# FMC_SDR_top.net
KiCad netlist of a schematic drawn in Altium Designer
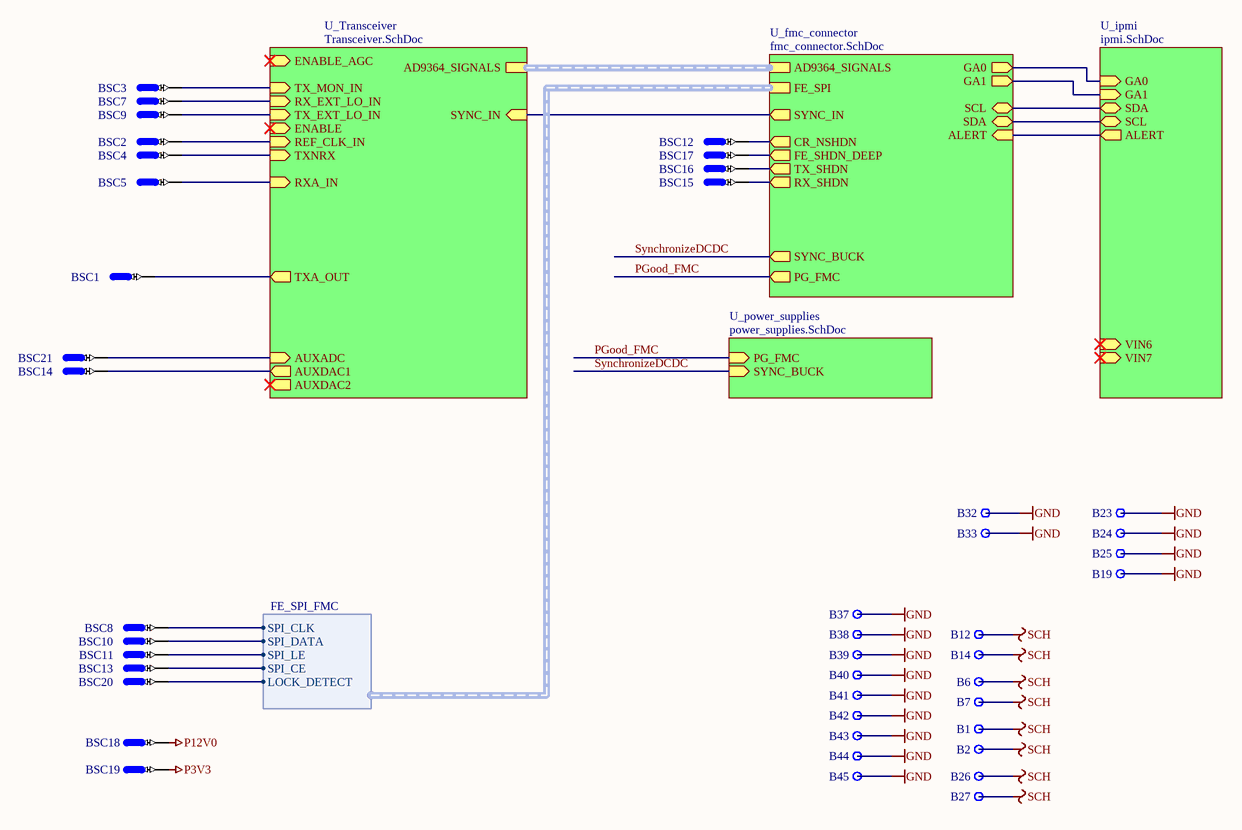
[diagram p0: FMC_SDR_top.SchDoc]

(export (version "E")
  (design (tool "Eeschema 10.0.6"))
  (components
    (comp (ref "B1")
      (value "Plated Hole")
      (footprint "MTG240_400")
      (description "Single Terminal Socket")
      (fields (field (name "PART NUMBER") "PLATED_HOLE2.4_PAD4.0") (field (name "AUTHOR") "CERN DEM JMW"))
      (libsource (lib "Eletro-mechanical") (part "Single Terminal Socket"))
    )
    (comp (ref "B2")
      (value "Plated Hole")
      (footprint "MTG240_400")
      (description "Single Terminal Socket")
      (fields (field (name "PART NUMBER") "PLATED_HOLE2.4_PAD4.0") (field (name "AUTHOR") "CERN DEM JMW"))
      (libsource (lib "Eletro-mechanical") (part "Single Terminal Socket"))
    )
    (comp (ref "B6")
      (value "Plated Hole")
      (footprint "MTG240_400")
      (description "Single Terminal Socket")
      (fields (field (name "PART NUMBER") "PLATED_HOLE2.4_PAD4.0") (field (name "AUTHOR") "CERN DEM JMW"))
      (libsource (lib "Eletro-mechanical") (part "Single Terminal Socket"))
    )
    (comp (ref "B7")
      (value "Plated Hole")
      (footprint "MTG240_400")
      (description "Single Terminal Socket")
      (fields (field (name "PART NUMBER") "PLATED_HOLE2.4_PAD4.0") (field (name "AUTHOR") "CERN DEM JMW"))
      (libsource (lib "Eletro-mechanical") (part "Single Terminal Socket"))
    )
    (comp (ref "B12")
      (value "Plated Hole")
      (footprint "MTG240_400")
      (description "Single Terminal Socket")
      (fields (field (name "PART NUMBER") "PLATED_HOLE2.4_PAD4.0") (field (name "AUTHOR") "CERN DEM JMW"))
      (libsource (lib "Eletro-mechanical") (part "Single Terminal Socket"))
    )
    (comp (ref "B14")
      (value "Plated Hole")
      (footprint "MTG240_400")
      (description "Single Terminal Socket")
      (fields (field (name "PART NUMBER") "PLATED_HOLE2.4_PAD4.0") (field (name "AUTHOR") "CERN DEM JMW"))
      (libsource (lib "Eletro-mechanical") (part "Single Terminal Socket"))
    )
    (comp (ref "B19")
      (value "Plated Hole")
      (footprint "MTG270_500")
      (description "Single Terminal Socket")
      (fields (field (name "PART NUMBER") "PLATED_HOLE2.7_PAD5.0") (field (name "AUTHOR") "CERN DEM JMW"))
      (libsource (lib "") (part "Single Terminal Socket_1"))
    )
    (comp (ref "B23")
      (value "Plated Hole")
      (footprint "MTG270_500")
      (description "Single Terminal Socket")
      (fields (field (name "PART NUMBER") "PLATED_HOLE2.7_PAD5.0") (field (name "AUTHOR") "CERN DEM JMW"))
      (libsource (lib "") (part "Single Terminal Socket_1"))
    )
    (comp (ref "B24")
      (value "Plated Hole")
      (footprint "MTG270_500")
      (description "Single Terminal Socket")
      (fields (field (name "PART NUMBER") "PLATED_HOLE2.7_PAD5.0") (field (name "AUTHOR") "CERN DEM JMW"))
      (libsource (lib "") (part "Single Terminal Socket_1"))
    )
    (comp (ref "B25")
      (value "Plated Hole")
      (footprint "MTG270_500")
      (description "Single Terminal Socket")
      (fields (field (name "PART NUMBER") "PLATED_HOLE2.7_PAD5.0") (field (name "AUTHOR") "CERN DEM JMW"))
      (libsource (lib "") (part "Single Terminal Socket_1"))
    )
    (comp (ref "B26")
      (value "Plated Hole")
      (footprint "MTG240_400")
      (description "Single Terminal Socket")
      (fields (field (name "PART NUMBER") "PLATED_HOLE2.4_PAD4.0") (field (name "AUTHOR") "CERN DEM JMW"))
      (libsource (lib "Eletro-mechanical") (part "Single Terminal Socket"))
    )
    (comp (ref "B27")
      (value "Plated Hole")
      (footprint "MTG240_400")
      (description "Single Terminal Socket")
      (fields (field (name "PART NUMBER") "PLATED_HOLE2.4_PAD4.0") (field (name "AUTHOR") "CERN DEM JMW"))
      (libsource (lib "Eletro-mechanical") (part "Single Terminal Socket"))
    )
    (comp (ref "B32")
      (value "Plated Hole")
      (footprint "MTG240_400")
      (description "Single Terminal Socket")
      (fields (field (name "PART NUMBER") "PLATED_HOLE2.4_PAD4.0") (field (name "AUTHOR") "CERN DEM JMW"))
      (libsource (lib "Eletro-mechanical") (part "Single Terminal Socket"))
    )
    (comp (ref "B33")
      (value "Plated Hole")
      (footprint "MTG240_400")
      (description "Single Terminal Socket")
      (fields (field (name "PART NUMBER") "PLATED_HOLE2.4_PAD4.0") (field (name "AUTHOR") "CERN DEM JMW"))
      (libsource (lib "Eletro-mechanical") (part "Single Terminal Socket"))
    )
    (comp (ref "B37")
      (value "Plated Hole")
      (footprint "MTG240_400")
      (description "Single Terminal Socket")
      (fields (field (name "PART NUMBER") "PLATED_HOLE2.4_PAD4.0") (field (name "AUTHOR") "CERN DEM JMW"))
      (libsource (lib "Eletro-mechanical") (part "Single Terminal Socket"))
    )
    (comp (ref "B38")
      (value "Plated Hole")
      (footprint "MTG240_400")
      (description "Single Terminal Socket")
      (fields (field (name "PART NUMBER") "PLATED_HOLE2.4_PAD4.0") (field (name "AUTHOR") "CERN DEM JMW"))
      (libsource (lib "Eletro-mechanical") (part "Single Terminal Socket"))
    )
    (comp (ref "B39")
      (value "Plated Hole")
      (footprint "MTG240_400")
      (description "Single Terminal Socket")
      (fields (field (name "PART NUMBER") "PLATED_HOLE2.4_PAD4.0") (field (name "AUTHOR") "CERN DEM JMW"))
      (libsource (lib "Eletro-mechanical") (part "Single Terminal Socket"))
    )
    (comp (ref "B40")
      (value "Plated Hole")
      (footprint "MTG240_400")
      (description "Single Terminal Socket")
      (fields (field (name "PART NUMBER") "PLATED_HOLE2.4_PAD4.0") (field (name "AUTHOR") "CERN DEM JMW"))
      (libsource (lib "Eletro-mechanical") (part "Single Terminal Socket"))
    )
    (comp (ref "B41")
      (value "Plated Hole")
      (footprint "MTG240_400")
      (description "Single Terminal Socket")
      (fields (field (name "PART NUMBER") "PLATED_HOLE2.4_PAD4.0") (field (name "AUTHOR") "CERN DEM JMW"))
      (libsource (lib "Eletro-mechanical") (part "Single Terminal Socket"))
    )
    (comp (ref "B42")
      (value "Plated Hole")
      (footprint "MTG240_400")
      (description "Single Terminal Socket")
      (fields (field (name "PART NUMBER") "PLATED_HOLE2.4_PAD4.0") (field (name "AUTHOR") "CERN DEM JMW"))
      (libsource (lib "Eletro-mechanical") (part "Single Terminal Socket"))
    )
    (comp (ref "B43")
      (value "Plated Hole")
      (footprint "MTG240_400")
      (description "Single Terminal Socket")
      (fields (field (name "PART NUMBER") "PLATED_HOLE2.4_PAD4.0") (field (name "AUTHOR") "CERN DEM JMW"))
      (libsource (lib "Eletro-mechanical") (part "Single Terminal Socket"))
    )
    (comp (ref "B44")
      (value "Plated Hole")
      (footprint "MTG240_400")
      (description "Single Terminal Socket")
      (fields (field (name "PART NUMBER") "PLATED_HOLE2.4_PAD4.0") (field (name "AUTHOR") "CERN DEM JMW"))
      (libsource (lib "Eletro-mechanical") (part "Single Terminal Socket"))
    )
    (comp (ref "B45")
      (value "Plated Hole")
      (footprint "MTG240_400")
      (description "Single Terminal Socket")
      (fields (field (name "PART NUMBER") "PLATED_HOLE2.4_PAD4.0") (field (name "AUTHOR") "CERN DEM JMW"))
      (libsource (lib "Eletro-mechanical") (part "Single Terminal Socket"))
    )
    (comp (ref "BSC1")
      (value "0603 Female")
      (footprint "PCB_CONN_0603F")
      (libsource (lib "FMC_SDR") (part "0603_female_BoardSolderConnector"))
    )
    (comp (ref "BSC2")
      (value "0603 Female")
      (footprint "PCB_CONN_0603F")
      (libsource (lib "FMC_SDR") (part "0603_female_BoardSolderConnector"))
    )
    (comp (ref "BSC3")
      (value "0603 Female")
      (footprint "PCB_CONN_0603F")
      (libsource (lib "FMC_SDR") (part "0603_female_BoardSolderConnector"))
    )
    (comp (ref "BSC4")
      (value "0603 Female")
      (footprint "PCB_CONN_0603F")
      (libsource (lib "FMC_SDR") (part "0603_female_BoardSolderConnector"))
    )
    (comp (ref "BSC5")
      (value "0603 Female")
      (footprint "PCB_CONN_0603F")
      (libsource (lib "FMC_SDR") (part "0603_female_BoardSolderConnector"))
    )
    (comp (ref "BSC7")
      (value "0603 Female")
      (footprint "PCB_CONN_0603F")
      (libsource (lib "FMC_SDR") (part "0603_female_BoardSolderConnector"))
    )
    (comp (ref "BSC8")
      (value "0603 Female")
      (footprint "PCB_CONN_0603F")
      (libsource (lib "FMC_SDR") (part "0603_female_BoardSolderConnector"))
    )
    (comp (ref "BSC9")
      (value "0603 Female")
      (footprint "PCB_CONN_0603F")
      (libsource (lib "FMC_SDR") (part "0603_female_BoardSolderConnector"))
    )
    (comp (ref "BSC10")
      (value "0603 Female")
      (footprint "PCB_CONN_0603F")
      (libsource (lib "FMC_SDR") (part "0603_female_BoardSolderConnector"))
    )
    (comp (ref "BSC11")
      (value "0603 Female")
      (footprint "PCB_CONN_0603F")
      (libsource (lib "FMC_SDR") (part "0603_female_BoardSolderConnector"))
    )
    (comp (ref "BSC12")
      (value "0603 Female")
      (footprint "PCB_CONN_0603F")
      (libsource (lib "FMC_SDR") (part "0603_female_BoardSolderConnector"))
    )
    (comp (ref "BSC13")
      (value "0603 Female")
      (footprint "PCB_CONN_0603F")
      (libsource (lib "FMC_SDR") (part "0603_female_BoardSolderConnector"))
    )
    (comp (ref "BSC14")
      (value "0603 Female")
      (footprint "PCB_CONN_0603F")
      (libsource (lib "FMC_SDR") (part "0603_female_BoardSolderConnector"))
    )
    (comp (ref "BSC15")
      (value "0603 Female")
      (footprint "PCB_CONN_0603F")
      (libsource (lib "FMC_SDR") (part "0603_female_BoardSolderConnector"))
    )
    (comp (ref "BSC16")
      (value "0603 Female")
      (footprint "PCB_CONN_0603F")
      (libsource (lib "FMC_SDR") (part "0603_female_BoardSolderConnector"))
    )
    (comp (ref "BSC17")
      (value "0603 Female")
      (footprint "PCB_CONN_0603F")
      (libsource (lib "FMC_SDR") (part "0603_female_BoardSolderConnector"))
    )
    (comp (ref "BSC18")
      (value "1206 Female")
      (footprint "PCB_CONN_1206F")
      (libsource (lib "FMC_SDR") (part "1206_female_BoardSolderConnector"))
    )
    (comp (ref "BSC19")
      (value "1206 Female")
      (footprint "PCB_CONN_1206F")
      (libsource (lib "FMC_SDR") (part "1206_female_BoardSolderConnector"))
    )
    (comp (ref "BSC20")
      (value "0603 Female")
      (footprint "PCB_CONN_0603F")
      (libsource (lib "FMC_SDR") (part "0603_female_BoardSolderConnector"))
    )
    (comp (ref "BSC21")
      (value "0603 Female")
      (footprint "PCB_CONN_0603F")
      (libsource (lib "FMC_SDR") (part "0603_female_BoardSolderConnector"))
    )
  )
  (nets
    (net (code "4") (name "/AUXADC") (class "Default")
      (node (ref "BSC21") (pin "1") (pinfunction "1_1") (pintype "bidirectional"))
    )
    (net (code "5") (name "/AUXDAC1") (class "Default")
      (node (ref "BSC14") (pin "1") (pinfunction "1_1") (pintype "bidirectional"))
    )
    (net (code "7") (name "/CR_NSHDN") (class "Default")
      (node (ref "BSC12") (pin "1") (pinfunction "1_1") (pintype "bidirectional"))
    )
    (net (code "10") (name "/FE_SHDN_DEEP") (class "Default")
      (node (ref "BSC17") (pin "1") (pinfunction "1_1") (pintype "bidirectional"))
    )
    (net (code "13") (name "/LOCK_DETECT") (class "Default")
      (node (ref "BSC20") (pin "1") (pinfunction "1_1") (pintype "bidirectional"))
    )
    (net (code "15") (name "/REF_CLK_IN") (class "Default")
      (node (ref "BSC2") (pin "1") (pinfunction "1_1") (pintype "bidirectional"))
    )
    (net (code "16") (name "/RXA_IN") (class "Default")
      (node (ref "BSC5") (pin "1") (pinfunction "1_1") (pintype "bidirectional"))
    )
    (net (code "17") (name "/RX_EXT_LO_IN") (class "Default")
      (node (ref "BSC7") (pin "1") (pinfunction "1_1") (pintype "bidirectional"))
    )
    (net (code "18") (name "/RX_SHDN") (class "Default")
      (node (ref "BSC15") (pin "1") (pinfunction "1_1") (pintype "bidirectional"))
    )
    (net (code "21") (name "/SPI_CE") (class "Default")
      (node (ref "BSC13") (pin "1") (pinfunction "1_1") (pintype "bidirectional"))
    )
    (net (code "22") (name "/SPI_CLK") (class "Default")
      (node (ref "BSC8") (pin "1") (pinfunction "1_1") (pintype "bidirectional"))
    )
    (net (code "23") (name "/SPI_DATA") (class "Default")
      (node (ref "BSC10") (pin "1") (pinfunction "1_1") (pintype "bidirectional"))
    )
    (net (code "24") (name "/SPI_LE") (class "Default")
      (node (ref "BSC11") (pin "1") (pinfunction "1_1") (pintype "bidirectional"))
    )
    (net (code "27") (name "/TXA_OUT") (class "Default")
      (node (ref "BSC1") (pin "1") (pinfunction "1_1") (pintype "bidirectional"))
    )
    (net (code "28") (name "/TXNRX") (class "Default")
      (node (ref "BSC4") (pin "1") (pinfunction "1_1") (pintype "bidirectional"))
    )
    (net (code "29") (name "/TX_EXT_LO_IN") (class "Default")
      (node (ref "BSC9") (pin "1") (pinfunction "1_1") (pintype "bidirectional"))
    )
    (net (code "30") (name "/TX_MON_IN") (class "Default")
      (node (ref "BSC3") (pin "1") (pinfunction "1_1") (pintype "bidirectional"))
    )
    (net (code "31") (name "/TX_SHDN") (class "Default")
      (node (ref "BSC16") (pin "1") (pinfunction "1_1") (pintype "bidirectional"))
    )
    (net (code "35") (name "GND") (class "Default")
      (node (ref "B19") (pin "1") (pinfunction "1_1") (pintype "bidirectional"))
      (node (ref "B23") (pin "1") (pinfunction "1_1") (pintype "bidirectional"))
      (node (ref "B24") (pin "1") (pinfunction "1_1") (pintype "bidirectional"))
      (node (ref "B25") (pin "1") (pinfunction "1_1") (pintype "bidirectional"))
      (node (ref "B32") (pin "1") (pinfunction "1_1") (pintype "passive"))
      (node (ref "B33") (pin "1") (pinfunction "1_1") (pintype "passive"))
      (node (ref "B37") (pin "1") (pinfunction "1_1") (pintype "passive"))
      (node (ref "B38") (pin "1") (pinfunction "1_1") (pintype "passive"))
      (node (ref "B39") (pin "1") (pinfunction "1_1") (pintype "passive"))
      (node (ref "B40") (pin "1") (pinfunction "1_1") (pintype "passive"))
      (node (ref "B41") (pin "1") (pinfunction "1_1") (pintype "passive"))
      (node (ref "B42") (pin "1") (pinfunction "1_1") (pintype "passive"))
      (node (ref "B43") (pin "1") (pinfunction "1_1") (pintype "passive"))
      (node (ref "B44") (pin "1") (pinfunction "1_1") (pintype "passive"))
      (node (ref "B45") (pin "1") (pinfunction "1_1") (pintype "passive"))
    )
    (net (code "36") (name "P3V3") (class "Default")
      (node (ref "BSC19") (pin "1") (pinfunction "1_1") (pintype "bidirectional"))
    )
    (net (code "37") (name "P12V0") (class "Default")
      (node (ref "BSC18") (pin "1") (pinfunction "1_1") (pintype "bidirectional"))
    )
    (net (code "38") (name "SCH") (class "Default")
      (node (ref "B1") (pin "1") (pinfunction "1_1") (pintype "passive"))
      (node (ref "B12") (pin "1") (pinfunction "1_1") (pintype "passive"))
      (node (ref "B14") (pin "1") (pinfunction "1_1") (pintype "passive"))
      (node (ref "B2") (pin "1") (pinfunction "1_1") (pintype "passive"))
      (node (ref "B26") (pin "1") (pinfunction "1_1") (pintype "passive"))
      (node (ref "B27") (pin "1") (pinfunction "1_1") (pintype "passive"))
      (node (ref "B6") (pin "1") (pinfunction "1_1") (pintype "passive"))
      (node (ref "B7") (pin "1") (pinfunction "1_1") (pintype "passive"))
    )
  )
)
